# HeaterController.net
KiCad netlist of a schematic drawn in EAGLE
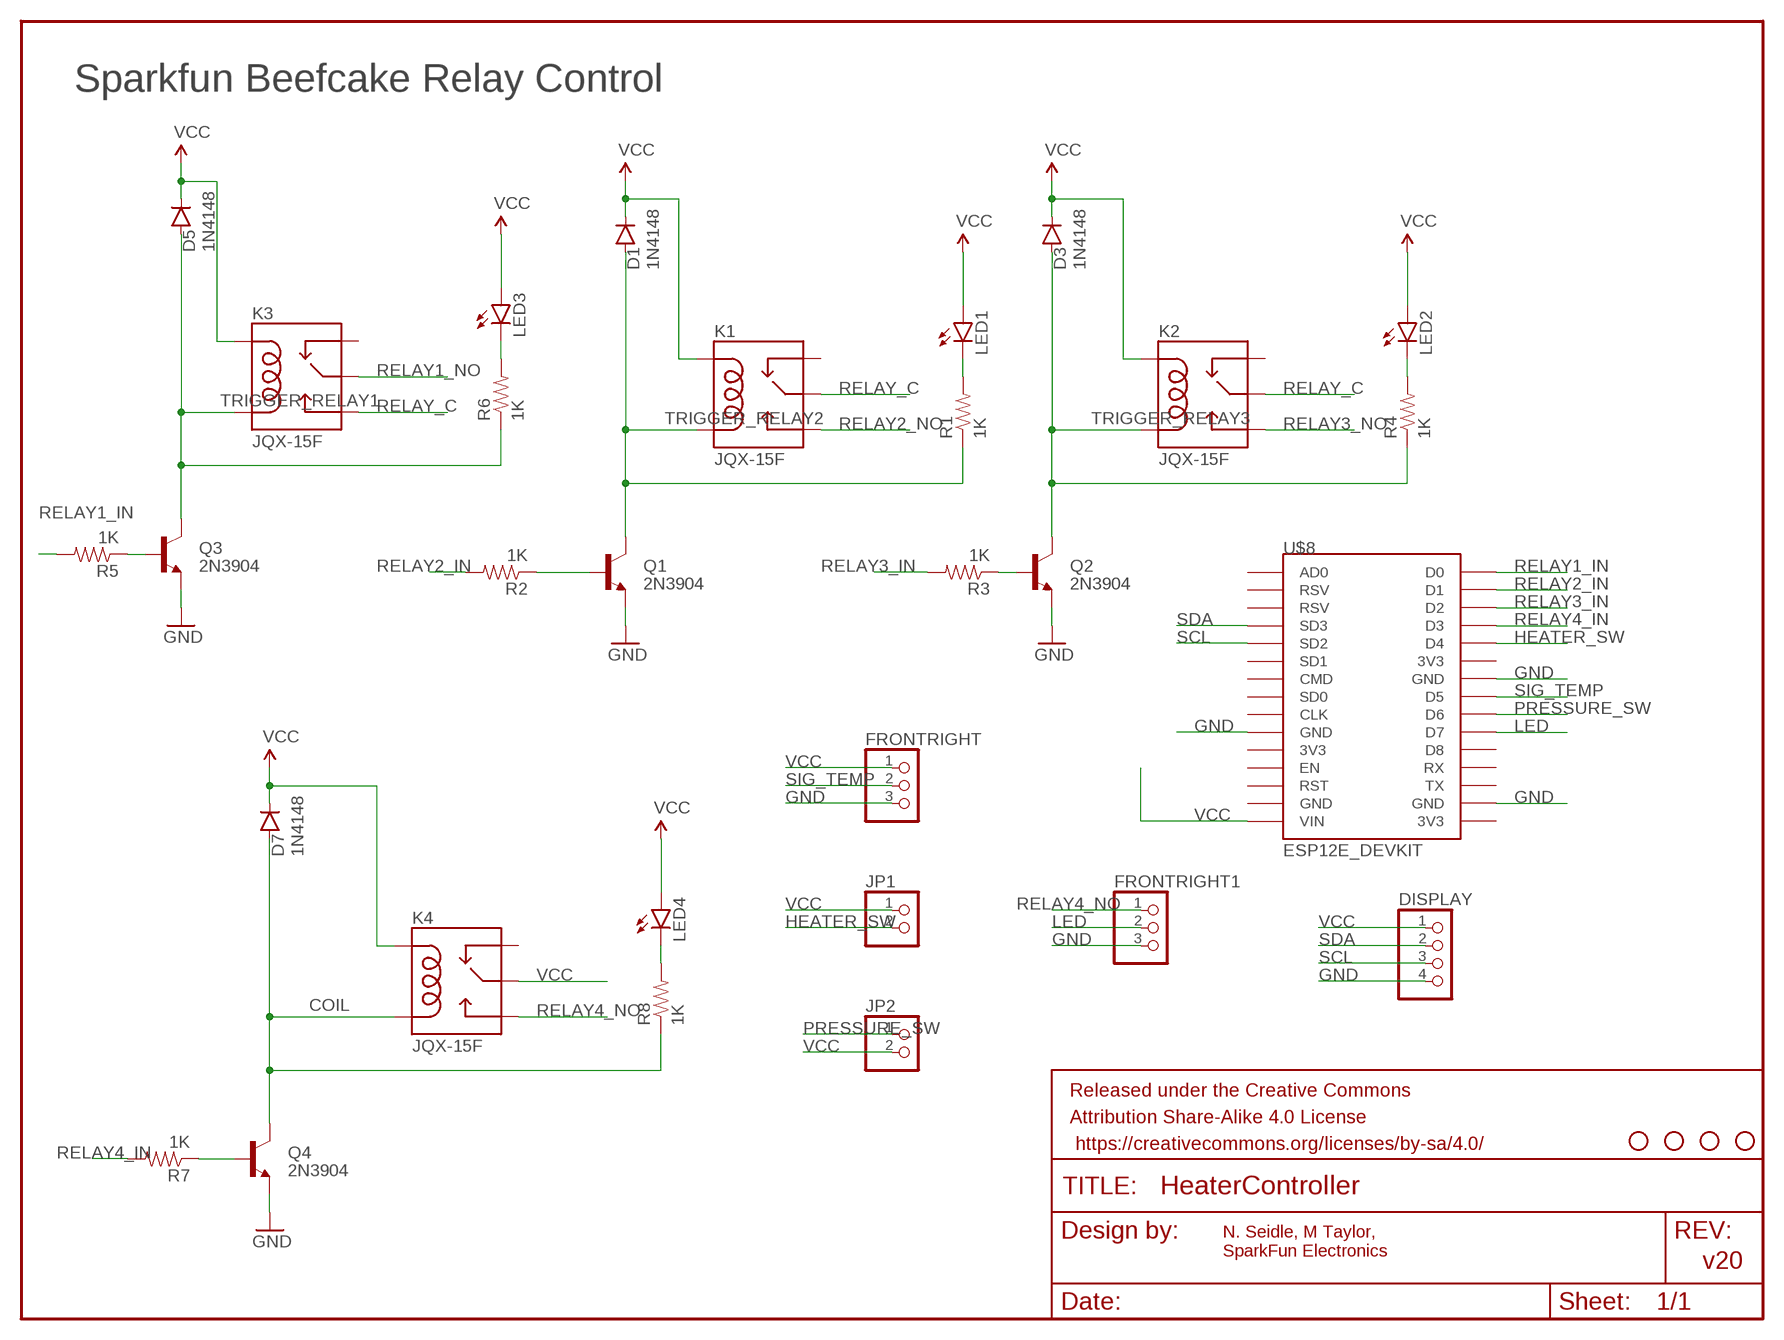
[diagram p0: schematic, sheet 1]

(export (version "E")
  (design (tool "Eeschema 10.0.6"))
  (components
    (comp (ref "D1")
      (value "1N4148")
      (footprint "eagle-import:DIODE-1N4148-KIT")
      (libsource (lib "eagle-import") (part "DIODEKIT"))
    )
    (comp (ref "D3")
      (value "1N4148")
      (footprint "eagle-import:DIODE-1N4148-KIT")
      (libsource (lib "eagle-import") (part "DIODEKIT"))
    )
    (comp (ref "D5")
      (value "1N4148")
      (footprint "eagle-import:DIODE-1N4148-KIT")
      (libsource (lib "eagle-import") (part "DIODEKIT"))
    )
    (comp (ref "D7")
      (value "1N4148")
      (footprint "eagle-import:DIODE-1N4148-KIT")
      (libsource (lib "eagle-import") (part "DIODEKIT"))
    )
    (comp (ref "DISPLAY")
      (value "PINHD-1X4")
      (footprint "eagle-import:1X04")
      (libsource (lib "eagle-import") (part "PINHD-1X4"))
    )
    (comp (ref "FRAME2")
      (value "FRAME-LETTER")
      (footprint "eagle-import:CREATIVE_COMMONS")
      (libsource (lib "eagle-import") (part "FRAME-LETTER"))
    )
    (comp (ref "FRONTRIGHT")
      (value "PINHD-1X3")
      (footprint "eagle-import:1X03")
      (libsource (lib "eagle-import") (part "PINHD-1X3"))
    )
    (comp (ref "FRONTRIGHT1")
      (value "PINHD-1X3")
      (footprint "eagle-import:1X03")
      (libsource (lib "eagle-import") (part "PINHD-1X3"))
    )
    (comp (ref "JP1")
      (value "PINHD-1X2")
      (footprint "eagle-import:1X02")
      (libsource (lib "eagle-import") (part "PINHD-1X2"))
    )
    (comp (ref "JP2")
      (value "PINHD-1X2")
      (footprint "eagle-import:1X02")
      (libsource (lib "eagle-import") (part "PINHD-1X2"))
    )
    (comp (ref "K1")
      (value "JQX-15F")
      (footprint "eagle-import:RELAY-T90")
      (libsource (lib "eagle-import") (part "RELAYPTH5"))
    )
    (comp (ref "K2")
      (value "JQX-15F")
      (footprint "eagle-import:RELAY-T90")
      (libsource (lib "eagle-import") (part "RELAYPTH5"))
    )
    (comp (ref "K3")
      (value "JQX-15F")
      (footprint "eagle-import:RELAY-T90")
      (libsource (lib "eagle-import") (part "RELAYPTH5"))
    )
    (comp (ref "K4")
      (value "JQX-15F")
      (footprint "eagle-import:RELAY-T90")
      (libsource (lib "eagle-import") (part "RELAYPTH5"))
    )
    (comp (ref "LED1")
      (value "LED5MM-KIT")
      (footprint "eagle-import:LED5MM-KIT")
      (fields (field (name "PROD_ID") "DIO-09529"))
      (libsource (lib "eagle-import") (part "LED5MM-KIT"))
    )
    (comp (ref "LED2")
      (value "LED5MM-KIT")
      (footprint "eagle-import:LED5MM-KIT")
      (fields (field (name "PROD_ID") "DIO-09529"))
      (libsource (lib "eagle-import") (part "LED5MM-KIT"))
    )
    (comp (ref "LED3")
      (value "LED5MM-KIT")
      (footprint "eagle-import:LED5MM-KIT")
      (fields (field (name "PROD_ID") "DIO-09529"))
      (libsource (lib "eagle-import") (part "LED5MM-KIT"))
    )
    (comp (ref "LED4")
      (value "LED5MM-KIT")
      (footprint "eagle-import:LED5MM-KIT")
      (fields (field (name "PROD_ID") "DIO-09529"))
      (libsource (lib "eagle-import") (part "LED5MM-KIT"))
    )
    (comp (ref "Q1")
      (value "2N3904")
      (footprint "eagle-import:TO-92-EZ")
      (libsource (lib "eagle-import") (part "TRANSISTOR_NPN2N3904-EZ"))
    )
    (comp (ref "Q2")
      (value "2N3904")
      (footprint "eagle-import:TO-92-EZ")
      (libsource (lib "eagle-import") (part "TRANSISTOR_NPN2N3904-EZ"))
    )
    (comp (ref "Q3")
      (value "2N3904")
      (footprint "eagle-import:TO-92-EZ")
      (libsource (lib "eagle-import") (part "TRANSISTOR_NPN2N3904-EZ"))
    )
    (comp (ref "Q4")
      (value "2N3904")
      (footprint "eagle-import:TO-92-EZ")
      (libsource (lib "eagle-import") (part "TRANSISTOR_NPN2N3904-EZ"))
    )
    (comp (ref "R1")
      (value "1K")
      (footprint "eagle-import:AXIAL-0.3EZ")
      (libsource (lib "eagle-import") (part "1KOHM-1/4W-1%(PTH)HORIZ-KIT"))
    )
    (comp (ref "R2")
      (value "1K")
      (footprint "eagle-import:AXIAL-0.3EZ")
      (libsource (lib "eagle-import") (part "1KOHM-1/4W-1%(PTH)HORIZ-KIT"))
    )
    (comp (ref "R3")
      (value "1K")
      (footprint "eagle-import:AXIAL-0.3EZ")
      (libsource (lib "eagle-import") (part "1KOHM-1/4W-1%(PTH)HORIZ-KIT"))
    )
    (comp (ref "R4")
      (value "1K")
      (footprint "eagle-import:AXIAL-0.3EZ")
      (libsource (lib "eagle-import") (part "1KOHM-1/4W-1%(PTH)HORIZ-KIT"))
    )
    (comp (ref "R5")
      (value "1K")
      (footprint "eagle-import:AXIAL-0.3EZ")
      (libsource (lib "eagle-import") (part "1KOHM-1/4W-1%(PTH)HORIZ-KIT"))
    )
    (comp (ref "R6")
      (value "1K")
      (footprint "eagle-import:AXIAL-0.3EZ")
      (libsource (lib "eagle-import") (part "1KOHM-1/4W-1%(PTH)HORIZ-KIT"))
    )
    (comp (ref "R7")
      (value "1K")
      (footprint "eagle-import:AXIAL-0.3EZ")
      (libsource (lib "eagle-import") (part "1KOHM-1/4W-1%(PTH)HORIZ-KIT"))
    )
    (comp (ref "R8")
      (value "1K")
      (footprint "eagle-import:AXIAL-0.3EZ")
      (libsource (lib "eagle-import") (part "1KOHM-1/4W-1%(PTH)HORIZ-KIT"))
    )
    (comp (ref "U$3")
      (value "STAND-OFF")
      (footprint "eagle-import:STAND-OFF")
      (libsource (lib "eagle-import") (part "STAND-OFF"))
    )
    (comp (ref "U$4")
      (value "STAND-OFF")
      (footprint "eagle-import:STAND-OFF")
      (libsource (lib "eagle-import") (part "STAND-OFF"))
    )
    (comp (ref "U$5")
      (value "STAND-OFF")
      (footprint "eagle-import:STAND-OFF")
      (libsource (lib "eagle-import") (part "STAND-OFF"))
    )
    (comp (ref "U$7")
      (value "STAND-OFF")
      (footprint "eagle-import:STAND-OFF")
      (libsource (lib "eagle-import") (part "STAND-OFF"))
    )
    (comp (ref "U$8")
      (value "ESP12E_DEVKIT")
      (footprint "eagle-import:ESP12E_DEVKIT")
      (libsource (lib "eagle-import") (part "ESP12E_DEVKIT"))
    )
  )
  (nets
    (net (code "1") (name "/COIL") (class "Default")
      (node (ref "D7") (pin "A") (pinfunction "A_A") (pintype "passive"))
      (node (ref "K4") (pin "COIL2") (pinfunction "COIL2_COIL2") (pintype "bidirectional"))
      (node (ref "Q4") (pin "3") (pinfunction "C_3") (pintype "passive"))
      (node (ref "R8") (pin "P$1") (pinfunction "1_P$1") (pintype "passive"))
    )
    (net (code "2") (name "/HEATER_SW") (class "Default")
      (node (ref "JP1") (pin "2") (pinfunction "2_2") (pintype "passive"))
      (node (ref "U$8") (pin "D4") (pinfunction "D4_D4") (pintype "bidirectional"))
    )
    (net (code "3") (name "/LED") (class "Default")
      (node (ref "FRONTRIGHT1") (pin "2") (pinfunction "2_2") (pintype "passive"))
      (node (ref "U$8") (pin "D7") (pinfunction "D7_D7") (pintype "bidirectional"))
    )
    (net (code "4") (name "/PRESSURE_SW") (class "Default")
      (node (ref "JP2") (pin "1") (pinfunction "1_1") (pintype "passive"))
      (node (ref "U$8") (pin "D6") (pinfunction "D6_D6") (pintype "bidirectional"))
    )
    (net (code "5") (name "/RELAY1_IN") (class "Default")
      (node (ref "R5") (pin "P$2") (pinfunction "2_P$2") (pintype "passive"))
      (node (ref "U$8") (pin "D0") (pinfunction "D0_D0") (pintype "bidirectional"))
    )
    (net (code "6") (name "/RELAY1_NO") (class "Default")
      (node (ref "K3") (pin "MAIN") (pinfunction "MAIN_MAIN") (pintype "bidirectional"))
    )
    (net (code "7") (name "/RELAY2_IN") (class "Default")
      (node (ref "R2") (pin "P$2") (pinfunction "2_P$2") (pintype "passive"))
      (node (ref "U$8") (pin "D1") (pinfunction "D1_D1") (pintype "bidirectional"))
    )
    (net (code "8") (name "/RELAY2_NO") (class "Default")
      (node (ref "K1") (pin "NO") (pinfunction "NO_NO") (pintype "bidirectional"))
    )
    (net (code "9") (name "/RELAY3_IN") (class "Default")
      (node (ref "R3") (pin "P$2") (pinfunction "2_P$2") (pintype "passive"))
      (node (ref "U$8") (pin "D2") (pinfunction "D2_D2") (pintype "bidirectional"))
    )
    (net (code "10") (name "/RELAY3_NO") (class "Default")
      (node (ref "K2") (pin "NO") (pinfunction "NO_NO") (pintype "bidirectional"))
    )
    (net (code "11") (name "/RELAY4_IN") (class "Default")
      (node (ref "R7") (pin "P$2") (pinfunction "2_P$2") (pintype "passive"))
      (node (ref "U$8") (pin "D3") (pinfunction "D3_D3") (pintype "bidirectional"))
    )
    (net (code "12") (name "/RELAY4_NO") (class "Default")
      (node (ref "FRONTRIGHT1") (pin "1") (pinfunction "1_1") (pintype "passive"))
      (node (ref "K4") (pin "NO") (pinfunction "NO_NO") (pintype "bidirectional"))
    )
    (net (code "13") (name "/RELAY_C") (class "Default")
      (node (ref "K1") (pin "MAIN") (pinfunction "MAIN_MAIN") (pintype "bidirectional"))
      (node (ref "K2") (pin "MAIN") (pinfunction "MAIN_MAIN") (pintype "bidirectional"))
      (node (ref "K3") (pin "NO") (pinfunction "NO_NO") (pintype "bidirectional"))
    )
    (net (code "14") (name "/SCL") (class "Default")
      (node (ref "DISPLAY") (pin "3") (pinfunction "3_3") (pintype "passive"))
      (node (ref "U$8") (pin "SD2") (pinfunction "SD2_SD2") (pintype "bidirectional"))
    )
    (net (code "15") (name "/SDA") (class "Default")
      (node (ref "DISPLAY") (pin "2") (pinfunction "2_2") (pintype "passive"))
      (node (ref "U$8") (pin "SD3") (pinfunction "SD3_SD3") (pintype "bidirectional"))
    )
    (net (code "16") (name "/SIG_TEMP") (class "Default")
      (node (ref "FRONTRIGHT") (pin "2") (pinfunction "2_2") (pintype "passive"))
      (node (ref "U$8") (pin "D5") (pinfunction "D5_D5") (pintype "bidirectional"))
    )
    (net (code "17") (name "/TRIGGER_RELAY1") (class "Default")
      (node (ref "D5") (pin "A") (pinfunction "A_A") (pintype "passive"))
      (node (ref "K3") (pin "COIL2") (pinfunction "COIL2_COIL2") (pintype "bidirectional"))
      (node (ref "Q3") (pin "3") (pinfunction "C_3") (pintype "passive"))
      (node (ref "R6") (pin "P$1") (pinfunction "1_P$1") (pintype "passive"))
    )
    (net (code "18") (name "/TRIGGER_RELAY2") (class "Default")
      (node (ref "D1") (pin "A") (pinfunction "A_A") (pintype "passive"))
      (node (ref "K1") (pin "COIL2") (pinfunction "COIL2_COIL2") (pintype "bidirectional"))
      (node (ref "Q1") (pin "3") (pinfunction "C_3") (pintype "passive"))
      (node (ref "R1") (pin "P$1") (pinfunction "1_P$1") (pintype "passive"))
    )
    (net (code "19") (name "/TRIGGER_RELAY3") (class "Default")
      (node (ref "D3") (pin "A") (pinfunction "A_A") (pintype "passive"))
      (node (ref "K2") (pin "COIL2") (pinfunction "COIL2_COIL2") (pintype "bidirectional"))
      (node (ref "Q2") (pin "3") (pinfunction "C_3") (pintype "passive"))
      (node (ref "R4") (pin "P$1") (pinfunction "1_P$1") (pintype "passive"))
    )
    (net (code "20") (name "GND") (class "Default")
      (node (ref "DISPLAY") (pin "4") (pinfunction "4_4") (pintype "passive"))
      (node (ref "FRONTRIGHT") (pin "3") (pinfunction "3_3") (pintype "passive"))
      (node (ref "FRONTRIGHT1") (pin "3") (pinfunction "3_3") (pintype "passive"))
      (node (ref "Q1") (pin "1") (pinfunction "E_1") (pintype "passive"))
      (node (ref "Q2") (pin "1") (pinfunction "E_1") (pintype "passive"))
      (node (ref "Q3") (pin "1") (pinfunction "E_1") (pintype "passive"))
      (node (ref "Q4") (pin "1") (pinfunction "E_1") (pintype "passive"))
      (node (ref "U$8") (pin "GND@0") (pinfunction "GND_GND@0") (pintype "bidirectional"))
      (node (ref "U$8") (pin "GND@2") (pinfunction "GND_GND@2") (pintype "bidirectional"))
      (node (ref "U$8") (pin "GND@3") (pinfunction "GND_GND@3") (pintype "bidirectional"))
    )
    (net (code "21") (name "Net-(LED1-C)") (class "Default")
      (node (ref "LED1") (pin "K") (pinfunction "C_K") (pintype "passive"))
      (node (ref "R1") (pin "P$2") (pinfunction "2_P$2") (pintype "passive"))
    )
    (net (code "22") (name "Net-(LED2-C)") (class "Default")
      (node (ref "LED2") (pin "K") (pinfunction "C_K") (pintype "passive"))
      (node (ref "R4") (pin "P$2") (pinfunction "2_P$2") (pintype "passive"))
    )
    (net (code "23") (name "Net-(LED3-C)") (class "Default")
      (node (ref "LED3") (pin "K") (pinfunction "C_K") (pintype "passive"))
      (node (ref "R6") (pin "P$2") (pinfunction "2_P$2") (pintype "passive"))
    )
    (net (code "24") (name "Net-(LED4-C)") (class "Default")
      (node (ref "LED4") (pin "K") (pinfunction "C_K") (pintype "passive"))
      (node (ref "R8") (pin "P$2") (pinfunction "2_P$2") (pintype "passive"))
    )
    (net (code "25") (name "Net-(Q1-B)") (class "Default")
      (node (ref "Q1") (pin "2") (pinfunction "B_2") (pintype "passive"))
      (node (ref "R2") (pin "P$1") (pinfunction "1_P$1") (pintype "passive"))
    )
    (net (code "26") (name "Net-(Q2-B)") (class "Default")
      (node (ref "Q2") (pin "2") (pinfunction "B_2") (pintype "passive"))
      (node (ref "R3") (pin "P$1") (pinfunction "1_P$1") (pintype "passive"))
    )
    (net (code "27") (name "Net-(Q3-B)") (class "Default")
      (node (ref "Q3") (pin "2") (pinfunction "B_2") (pintype "passive"))
      (node (ref "R5") (pin "P$1") (pinfunction "1_P$1") (pintype "passive"))
    )
    (net (code "28") (name "Net-(Q4-B)") (class "Default")
      (node (ref "Q4") (pin "2") (pinfunction "B_2") (pintype "passive"))
      (node (ref "R7") (pin "P$1") (pinfunction "1_P$1") (pintype "passive"))
    )
    (net (code "29") (name "VCC") (class "Default")
      (node (ref "D1") (pin "C") (pinfunction "C_C") (pintype "passive"))
      (node (ref "D3") (pin "C") (pinfunction "C_C") (pintype "passive"))
      (node (ref "D5") (pin "C") (pinfunction "C_C") (pintype "passive"))
      (node (ref "D7") (pin "C") (pinfunction "C_C") (pintype "passive"))
      (node (ref "DISPLAY") (pin "1") (pinfunction "1_1") (pintype "passive"))
      (node (ref "FRONTRIGHT") (pin "1") (pinfunction "1_1") (pintype "passive"))
      (node (ref "JP1") (pin "1") (pinfunction "1_1") (pintype "passive"))
      (node (ref "JP2") (pin "2") (pinfunction "2_2") (pintype "passive"))
      (node (ref "K1") (pin "COIL1") (pinfunction "COIL1_COIL1") (pintype "bidirectional"))
      (node (ref "K2") (pin "COIL1") (pinfunction "COIL1_COIL1") (pintype "bidirectional"))
      (node (ref "K3") (pin "COIL1") (pinfunction "COIL1_COIL1") (pintype "bidirectional"))
      (node (ref "K4") (pin "COIL1") (pinfunction "COIL1_COIL1") (pintype "bidirectional"))
      (node (ref "K4") (pin "MAIN") (pinfunction "MAIN_MAIN") (pintype "bidirectional"))
      (node (ref "LED1") (pin "A") (pinfunction "A_A") (pintype "passive"))
      (node (ref "LED2") (pin "A") (pinfunction "A_A") (pintype "passive"))
      (node (ref "LED3") (pin "A") (pinfunction "A_A") (pintype "passive"))
      (node (ref "LED4") (pin "A") (pinfunction "A_A") (pintype "passive"))
      (node (ref "U$8") (pin "VIN") (pinfunction "VIN_VIN") (pintype "bidirectional"))
    )
    (net (code "30") (name "unconnected-(K1-PadNC)") (class "Default")
      (node (ref "K1") (pin "NC") (pinfunction "NC_NC") (pintype "bidirectional"))
    )
    (net (code "31") (name "unconnected-(K2-PadNC)") (class "Default")
      (node (ref "K2") (pin "NC") (pinfunction "NC_NC") (pintype "bidirectional"))
    )
    (net (code "32") (name "unconnected-(K3-PadNC)") (class "Default")
      (node (ref "K3") (pin "NC") (pinfunction "NC_NC") (pintype "bidirectional"))
    )
    (net (code "33") (name "unconnected-(K4-PadNC)") (class "Default")
      (node (ref "K4") (pin "NC") (pinfunction "NC_NC") (pintype "bidirectional"))
    )
    (net (code "34") (name "unconnected-(U$8-3V3-Pad3V3@0)") (class "Default")
      (node (ref "U$8") (pin "3V3@0") (pinfunction "3V3_3V3@0") (pintype "bidirectional"))
    )
    (net (code "35") (name "unconnected-(U$8-3V3-Pad3V3@1)") (class "Default")
      (node (ref "U$8") (pin "3V3@1") (pinfunction "3V3_3V3@1") (pintype "bidirectional"))
    )
    (net (code "36") (name "unconnected-(U$8-3V3-Pad3V3@2)") (class "Default")
      (node (ref "U$8") (pin "3V3@2") (pinfunction "3V3_3V3@2") (pintype "bidirectional"))
    )
    (net (code "37") (name "unconnected-(U$8-GND-PadGND@1)") (class "Default")
      (node (ref "U$8") (pin "GND@1") (pinfunction "GND_GND@1") (pintype "bidirectional"))
    )
    (net (code "38") (name "unconnected-(U$8-PadAD0)") (class "Default")
      (node (ref "U$8") (pin "AD0") (pinfunction "AD0_AD0") (pintype "bidirectional"))
    )
    (net (code "39") (name "unconnected-(U$8-PadCLK)") (class "Default")
      (node (ref "U$8") (pin "CLK") (pinfunction "CLK_CLK") (pintype "bidirectional"))
    )
    (net (code "40") (name "unconnected-(U$8-PadCMD)") (class "Default")
      (node (ref "U$8") (pin "CMD") (pinfunction "CMD_CMD") (pintype "bidirectional"))
    )
    (net (code "41") (name "unconnected-(U$8-PadD8)") (class "Default")
      (node (ref "U$8") (pin "D8") (pinfunction "D8_D8") (pintype "bidirectional"))
    )
    (net (code "42") (name "unconnected-(U$8-PadEN)") (class "Default")
      (node (ref "U$8") (pin "EN") (pinfunction "EN_EN") (pintype "bidirectional"))
    )
    (net (code "43") (name "unconnected-(U$8-PadRST)") (class "Default")
      (node (ref "U$8") (pin "RST") (pinfunction "RST_RST") (pintype "bidirectional"))
    )
    (net (code "44") (name "unconnected-(U$8-PadRX)") (class "Default")
      (node (ref "U$8") (pin "RX") (pinfunction "RX_RX") (pintype "bidirectional"))
    )
    (net (code "45") (name "unconnected-(U$8-PadSD0)") (class "Default")
      (node (ref "U$8") (pin "SD0") (pinfunction "SD0_SD0") (pintype "bidirectional"))
    )
    (net (code "46") (name "unconnected-(U$8-PadSD1)") (class "Default")
      (node (ref "U$8") (pin "SD1") (pinfunction "SD1_SD1") (pintype "bidirectional"))
    )
    (net (code "47") (name "unconnected-(U$8-PadTX)") (class "Default")
      (node (ref "U$8") (pin "TX") (pinfunction "TX_TX") (pintype "bidirectional"))
    )
    (net (code "48") (name "unconnected-(U$8-RSV-PadRSV@0)") (class "Default")
      (node (ref "U$8") (pin "RSV@0") (pinfunction "RSV_RSV@0") (pintype "bidirectional"))
    )
    (net (code "49") (name "unconnected-(U$8-RSV-PadRSV@1)") (class "Default")
      (node (ref "U$8") (pin "RSV@1") (pinfunction "RSV_RSV@1") (pintype "bidirectional"))
    )
  )
)
